# MCU.net
KiCad netlist of a schematic drawn in Altium Designer
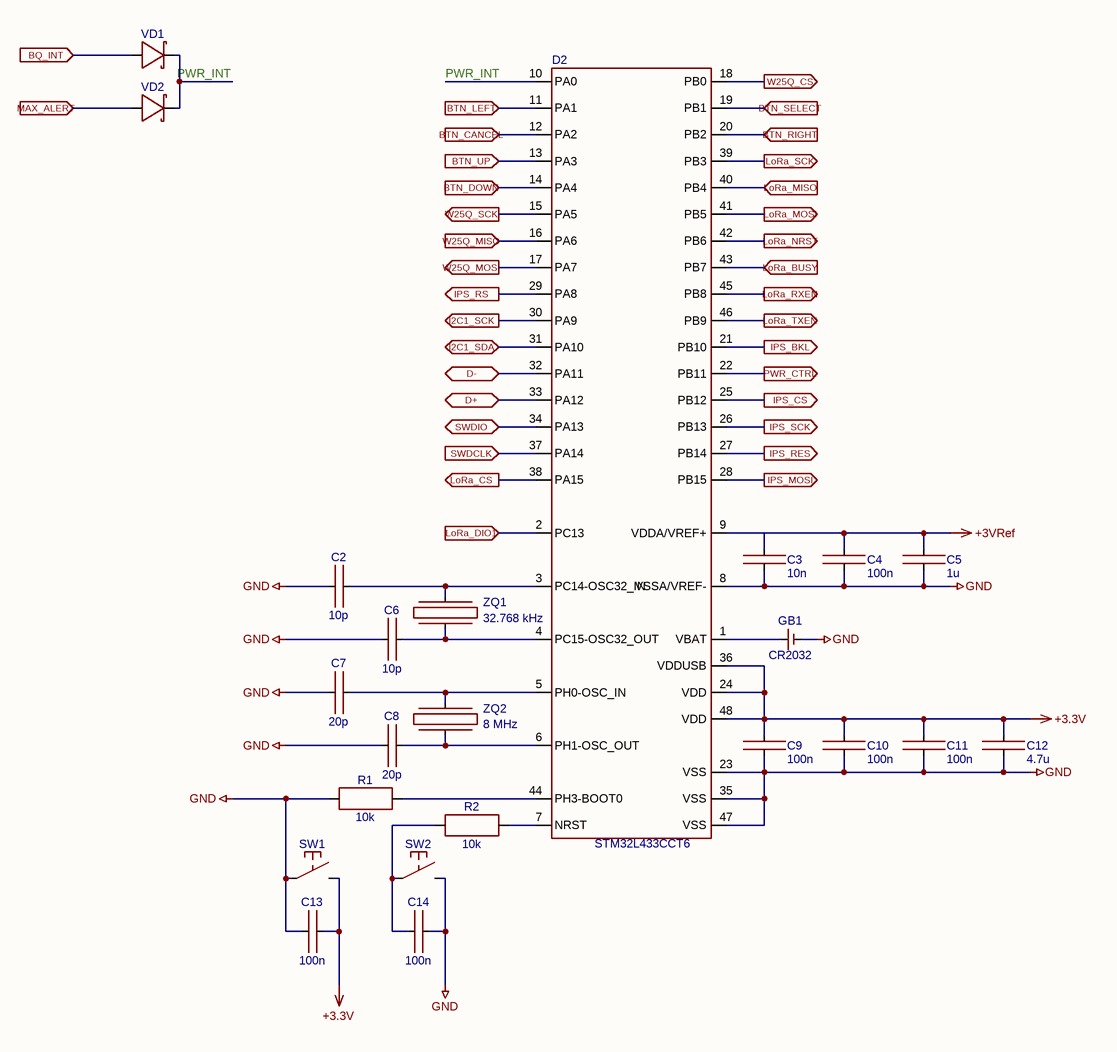
[diagram p0: MCU.SchDoc]

(export (version "E")
  (design (tool "Eeschema 10.0.6"))
  (components
    (comp (ref "C2")
      (value "10p")
      (footprint "CAPC1608X09N")
      (description "GRM1885C1H100JA01D")
      (libsource (lib "Capasitors") (part "C0603-10p-50V-NPO-5%"))
    )
    (comp (ref "C3")
      (value "10n")
      (footprint "CAPC1608X09N")
      (description "GRM188R72A103KA01D")
      (libsource (lib "Capasitors") (part "C0603-10n-100V-X7R-10%"))
    )
    (comp (ref "C4")
      (value "100n")
      (footprint "CAPC1608X09N")
      (description "GRM188R71E104KA01D")
      (libsource (lib "Capasitors") (part "C0603-100n-25V-X7R-10%"))
    )
    (comp (ref "C5")
      (value "1u")
      (footprint "CAPC1608X09N")
      (description "GRM188R71E105KA12D")
      (libsource (lib "Capasitors") (part "C0603-1u-25V-X7R-10%"))
    )
    (comp (ref "C6")
      (value "10p")
      (footprint "CAPC1608X09N")
      (description "GRM1885C1H100JA01D")
      (libsource (lib "Capasitors") (part "C0603-10p-50V-NPO-5%"))
    )
    (comp (ref "C7")
      (value "20p")
      (footprint "CAPC1608X09N")
      (description "GRM1885C1H200J")
      (libsource (lib "Capasitors") (part "C0603-20p-50V-NPO-5%"))
    )
    (comp (ref "C8")
      (value "20p")
      (footprint "CAPC1608X09N")
      (description "GRM1885C1H200J")
      (libsource (lib "Capasitors") (part "C0603-20p-50V-NPO-5%"))
    )
    (comp (ref "C9")
      (value "100n")
      (footprint "CAPC1608X09N")
      (description "GRM188R71E104KA01D")
      (libsource (lib "Capasitors") (part "C0603-100n-25V-X7R-10%"))
    )
    (comp (ref "C10")
      (value "100n")
      (footprint "CAPC1608X09N")
      (description "GRM188R71E104KA01D")
      (libsource (lib "Capasitors") (part "C0603-100n-25V-X7R-10%"))
    )
    (comp (ref "C11")
      (value "100n")
      (footprint "CAPC1608X09N")
      (description "GRM188R71E104KA01D")
      (libsource (lib "Capasitors") (part "C0603-100n-25V-X7R-10%"))
    )
    (comp (ref "C12")
      (value "4.7u")
      (footprint "CAPC1608X09N")
      (description "GRM188R61A475K")
      (libsource (lib "Capasitors") (part "C0603-4.7u-10V-X5R-10%"))
    )
    (comp (ref "C13")
      (value "100n")
      (footprint "CAPC1608X09N")
      (description "GRM188R71E104KA01D")
      (libsource (lib "Capasitors") (part "C0603-100n-25V-X7R-10%"))
    )
    (comp (ref "C14")
      (value "100n")
      (footprint "CAPC1608X09N")
      (description "GRM188R71E104KA01D")
      (libsource (lib "Capasitors") (part "C0603-100n-25V-X7R-10%"))
    )
    (comp (ref "D2")
      (value "STM32L433CCT6")
      (footprint "STM LQFP-48 (5B_ME_V2)")
      (libsource (lib "Integrated Circuits") (part "STM32L433CCT6"))
    )
    (comp (ref "GB1")
      (value "CR2032")
      (footprint "KLS5-CR2032-03")
      (libsource (lib "Battery Holders") (part "KLS5-CR2032-03"))
    )
    (comp (ref "R1")
      (value "10k")
      (footprint "RESC2012X05N")
      (libsource (lib "Resistors") (part "R-0805-10k-5%"))
    )
    (comp (ref "R2")
      (value "10k")
      (footprint "RESC2012X05N")
      (libsource (lib "Resistors") (part "R-0805-10k-5%"))
    )
    (comp (ref "SW1")
      (value "FSM1SM")
      (footprint "FSM1SM")
      (description "1437566-3 (FSMSM), Кнопка тактовая h=4.6 мм SMD SPST")
      (libsource (lib "Buttons") (part "FSM1SM"))
    )
    (comp (ref "SW2")
      (value "FSM1SM")
      (footprint "FSM1SM")
      (description "1437566-3 (FSMSM), Кнопка тактовая h=4.6 мм SMD SPST")
      (libsource (lib "Buttons") (part "FSM1SM"))
    )
    (comp (ref "VD1")
      (value "BAR6402VH6327XTSA1")
      (footprint "INFENION SC79")
      (libsource (lib "Diodes") (part "BAR6402VH6327XTSA1"))
    )
    (comp (ref "VD2")
      (value "BAR6402VH6327XTSA1")
      (footprint "INFENION SC79")
      (libsource (lib "Diodes") (part "BAR6402VH6327XTSA1"))
    )
    (comp (ref "ZQ1")
      (value "32.768 kHz")
      (footprint "NX3215SA")
      (description "32.768 кГц, 20ppm, 7пФ, 70кОм, -40...+85°C, SMD 3.2*1.5*0.8мм, Кварцевый резонатор")
      (libsource (lib "Oscillators") (part "NX3215SA"))
    )
    (comp (ref "ZQ2")
      (value "8 МHz")
      (footprint "NX5032GA")
      (description "8 МГц, 30/20ppm, 8пФ, -40...+85°C, SMD 5.0*3.2*1.3мм, Кварцевый резонатор")
      (libsource (lib "Oscillators") (part "NX5032GA"))
    )
  )
  (nets
    (net (code "1") (name "+3.3V") (class "Default")
      (node (ref "C10") (pin "2") (pinfunction "2_2") (pintype "passive"))
      (node (ref "C11") (pin "2") (pinfunction "2_2") (pintype "passive"))
      (node (ref "C12") (pin "2") (pinfunction "2_2") (pintype "passive"))
      (node (ref "C13") (pin "2") (pinfunction "2_2") (pintype "passive"))
      (node (ref "C9") (pin "2") (pinfunction "2_2") (pintype "passive"))
      (node (ref "D2") (pin "24") (pinfunction "VDD_24") (pintype "passive"))
      (node (ref "D2") (pin "36") (pinfunction "VDDUSB_36") (pintype "passive"))
      (node (ref "D2") (pin "48") (pinfunction "VDD_48") (pintype "passive"))
      (node (ref "SW1") (pin "1") (pinfunction "1_1") (pintype "passive"))
    )
    (net (code "2") (name "+3VRef") (class "Default")
      (node (ref "C3") (pin "2") (pinfunction "2_2") (pintype "passive"))
      (node (ref "C4") (pin "2") (pinfunction "2_2") (pintype "passive"))
      (node (ref "C5") (pin "2") (pinfunction "2_2") (pintype "passive"))
      (node (ref "D2") (pin "9") (pinfunction "VDDA/VREF+_9") (pintype "passive"))
    )
    (net (code "3") (name "/BQ_INT") (class "Default")
      (node (ref "VD1") (pin "2") (pinfunction "2_2") (pintype "passive"))
    )
    (net (code "4") (name "/BTN_CANCEL") (class "Default")
      (node (ref "D2") (pin "12") (pinfunction "PA2_12") (pintype "passive"))
    )
    (net (code "5") (name "/BTN_DOWN") (class "Default")
      (node (ref "D2") (pin "14") (pinfunction "PA4_14") (pintype "passive"))
    )
    (net (code "6") (name "/BTN_LEFT") (class "Default")
      (node (ref "D2") (pin "11") (pinfunction "PA1_11") (pintype "passive"))
    )
    (net (code "7") (name "/BTN_RIGHT") (class "Default")
      (node (ref "D2") (pin "20") (pinfunction "PB2_20") (pintype "passive"))
    )
    (net (code "8") (name "/BTN_SELECT") (class "Default")
      (node (ref "D2") (pin "19") (pinfunction "PB1_19") (pintype "passive"))
    )
    (net (code "9") (name "/BTN_UP") (class "Default")
      (node (ref "D2") (pin "13") (pinfunction "PA3_13") (pintype "passive"))
    )
    (net (code "10") (name "/D+") (class "Default")
      (node (ref "D2") (pin "33") (pinfunction "PA12_33") (pintype "passive"))
    )
    (net (code "11") (name "/D-") (class "Default")
      (node (ref "D2") (pin "32") (pinfunction "PA11_32") (pintype "passive"))
    )
    (net (code "12") (name "/I2C1_SCK") (class "Default")
      (node (ref "D2") (pin "30") (pinfunction "PA9_30") (pintype "passive"))
    )
    (net (code "13") (name "/I2C1_SDA") (class "Default")
      (node (ref "D2") (pin "31") (pinfunction "PA10_31") (pintype "passive"))
    )
    (net (code "14") (name "/IPS_BKL") (class "Default")
      (node (ref "D2") (pin "21") (pinfunction "PB10_21") (pintype "passive"))
    )
    (net (code "15") (name "/IPS_CS") (class "Default")
      (node (ref "D2") (pin "25") (pinfunction "PB12_25") (pintype "passive"))
    )
    (net (code "16") (name "/IPS_MOSI") (class "Default")
      (node (ref "D2") (pin "28") (pinfunction "PB15_28") (pintype "passive"))
    )
    (net (code "17") (name "/IPS_RES") (class "Default")
      (node (ref "D2") (pin "27") (pinfunction "PB14_27") (pintype "passive"))
    )
    (net (code "18") (name "/IPS_RS") (class "Default")
      (node (ref "D2") (pin "29") (pinfunction "PA8_29") (pintype "passive"))
    )
    (net (code "19") (name "/IPS_SCK") (class "Default")
      (node (ref "D2") (pin "26") (pinfunction "PB13_26") (pintype "passive"))
    )
    (net (code "20") (name "/LoRa_BUSY") (class "Default")
      (node (ref "D2") (pin "43") (pinfunction "PB7_43") (pintype "passive"))
    )
    (net (code "21") (name "/LoRa_CS") (class "Default")
      (node (ref "D2") (pin "38") (pinfunction "PA15_38") (pintype "passive"))
    )
    (net (code "22") (name "/LoRa_DIO1") (class "Default")
      (node (ref "D2") (pin "2") (pinfunction "PC13_2") (pintype "passive"))
    )
    (net (code "23") (name "/LoRa_MISO") (class "Default")
      (node (ref "D2") (pin "40") (pinfunction "PB4_40") (pintype "passive"))
    )
    (net (code "24") (name "/LoRa_MOSI") (class "Default")
      (node (ref "D2") (pin "41") (pinfunction "PB5_41") (pintype "passive"))
    )
    (net (code "25") (name "/LoRa_NRST") (class "Default")
      (node (ref "D2") (pin "42") (pinfunction "PB6_42") (pintype "passive"))
    )
    (net (code "26") (name "/LoRa_RXEN") (class "Default")
      (node (ref "D2") (pin "45") (pinfunction "PB8_45") (pintype "passive"))
    )
    (net (code "27") (name "/LoRa_SCK") (class "Default")
      (node (ref "D2") (pin "39") (pinfunction "PB3_39") (pintype "passive"))
    )
    (net (code "28") (name "/LoRa_TXEN") (class "Default")
      (node (ref "D2") (pin "46") (pinfunction "PB9_46") (pintype "passive"))
    )
    (net (code "29") (name "/MAX_ALERT") (class "Default")
      (node (ref "VD2") (pin "2") (pinfunction "2_2") (pintype "passive"))
    )
    (net (code "30") (name "/PWR_CTRL") (class "Default")
      (node (ref "D2") (pin "22") (pinfunction "PB11_22") (pintype "passive"))
    )
    (net (code "31") (name "/PWR_INT") (class "Default")
      (node (ref "D2") (pin "10") (pinfunction "PA0_10") (pintype "passive"))
      (node (ref "VD1") (pin "1") (pinfunction "1_1") (pintype "passive"))
      (node (ref "VD2") (pin "1") (pinfunction "1_1") (pintype "passive"))
    )
    (net (code "32") (name "/SWDCLK") (class "Default")
      (node (ref "D2") (pin "37") (pinfunction "PA14_37") (pintype "passive"))
    )
    (net (code "33") (name "/SWDIO") (class "Default")
      (node (ref "D2") (pin "34") (pinfunction "PA13_34") (pintype "passive"))
    )
    (net (code "34") (name "/W25Q_CS") (class "Default")
      (node (ref "D2") (pin "18") (pinfunction "PB0_18") (pintype "passive"))
    )
    (net (code "35") (name "/W25Q_MISO") (class "Default")
      (node (ref "D2") (pin "16") (pinfunction "PA6_16") (pintype "passive"))
    )
    (net (code "36") (name "/W25Q_MOSI") (class "Default")
      (node (ref "D2") (pin "17") (pinfunction "PA7_17") (pintype "passive"))
    )
    (net (code "37") (name "/W25Q_SCK") (class "Default")
      (node (ref "D2") (pin "15") (pinfunction "PA5_15") (pintype "passive"))
    )
    (net (code "38") (name "GND") (class "Default")
      (node (ref "C10") (pin "1") (pinfunction "1_1") (pintype "passive"))
      (node (ref "C11") (pin "1") (pinfunction "1_1") (pintype "passive"))
      (node (ref "C12") (pin "1") (pinfunction "1_1") (pintype "passive"))
      (node (ref "C13") (pin "1") (pinfunction "1_1") (pintype "passive"))
      (node (ref "C14") (pin "2") (pinfunction "2_2") (pintype "passive"))
      (node (ref "C2") (pin "1") (pinfunction "1_1") (pintype "passive"))
      (node (ref "C3") (pin "1") (pinfunction "1_1") (pintype "passive"))
      (node (ref "C4") (pin "1") (pinfunction "1_1") (pintype "passive"))
      (node (ref "C5") (pin "1") (pinfunction "1_1") (pintype "passive"))
      (node (ref "C6") (pin "1") (pinfunction "1_1") (pintype "passive"))
      (node (ref "C7") (pin "1") (pinfunction "1_1") (pintype "passive"))
      (node (ref "C8") (pin "1") (pinfunction "1_1") (pintype "passive"))
      (node (ref "C9") (pin "1") (pinfunction "1_1") (pintype "passive"))
      (node (ref "D2") (pin "23") (pinfunction "VSS_23") (pintype "passive"))
      (node (ref "D2") (pin "35") (pinfunction "VSS_35") (pintype "passive"))
      (node (ref "D2") (pin "47") (pinfunction "VSS_47") (pintype "passive"))
      (node (ref "D2") (pin "8") (pinfunction "VSSA/VREF-_8") (pintype "passive"))
      (node (ref "GB1") (pin "0") (pinfunction "0_0") (pintype "passive"))
      (node (ref "R1") (pin "1") (pinfunction "1_1") (pintype "passive"))
      (node (ref "SW1") (pin "0") (pinfunction "0_0") (pintype "passive"))
      (node (ref "SW2") (pin "1") (pinfunction "1_1") (pintype "passive"))
    )
    (net (code "39") (name "Net-(C14-Pad1)") (class "Default")
      (node (ref "C14") (pin "1") (pinfunction "1_1") (pintype "passive"))
      (node (ref "R2") (pin "1") (pinfunction "1_1") (pintype "passive"))
      (node (ref "SW2") (pin "0") (pinfunction "0_0") (pintype "passive"))
    )
    (net (code "40") (name "Net-(D2-NRST)") (class "Default")
      (node (ref "D2") (pin "7") (pinfunction "NRST_7") (pintype "passive"))
      (node (ref "R2") (pin "2") (pinfunction "2_2") (pintype "passive"))
    )
    (net (code "41") (name "Net-(D2-PC14-OSC32_IN)") (class "Default")
      (node (ref "C2") (pin "2") (pinfunction "2_2") (pintype "passive"))
      (node (ref "D2") (pin "3") (pinfunction "PC14-OSC32_IN_3") (pintype "passive"))
      (node (ref "ZQ1") (pin "1") (pinfunction "1_1") (pintype "passive"))
    )
    (net (code "42") (name "Net-(D2-PC15-OSC32_OUT)") (class "Default")
      (node (ref "C6") (pin "2") (pinfunction "2_2") (pintype "passive"))
      (node (ref "D2") (pin "4") (pinfunction "PC15-OSC32_OUT_4") (pintype "passive"))
      (node (ref "ZQ1") (pin "0") (pinfunction "0_0") (pintype "passive"))
    )
    (net (code "43") (name "Net-(D2-PH0-OSC_IN)") (class "Default")
      (node (ref "C7") (pin "2") (pinfunction "2_2") (pintype "passive"))
      (node (ref "D2") (pin "5") (pinfunction "PH0-OSC_IN_5") (pintype "passive"))
      (node (ref "ZQ2") (pin "1") (pinfunction "1_1") (pintype "passive"))
    )
    (net (code "44") (name "Net-(D2-PH1-OSC_OUT)") (class "Default")
      (node (ref "C8") (pin "2") (pinfunction "2_2") (pintype "passive"))
      (node (ref "D2") (pin "6") (pinfunction "PH1-OSC_OUT_6") (pintype "passive"))
      (node (ref "ZQ2") (pin "0") (pinfunction "0_0") (pintype "passive"))
    )
    (net (code "45") (name "Net-(D2-PH3-BOOT0)") (class "Default")
      (node (ref "D2") (pin "44") (pinfunction "PH3-BOOT0_44") (pintype "passive"))
      (node (ref "R1") (pin "2") (pinfunction "2_2") (pintype "passive"))
    )
    (net (code "46") (name "Net-(D2-VBAT)") (class "Default")
      (node (ref "D2") (pin "1") (pinfunction "VBAT_1") (pintype "passive"))
      (node (ref "GB1") (pin "1") (pinfunction "1_1") (pintype "passive"))
    )
  )
)
